# DischargeModule.net
KiCad netlist of a schematic drawn in Altium Designer
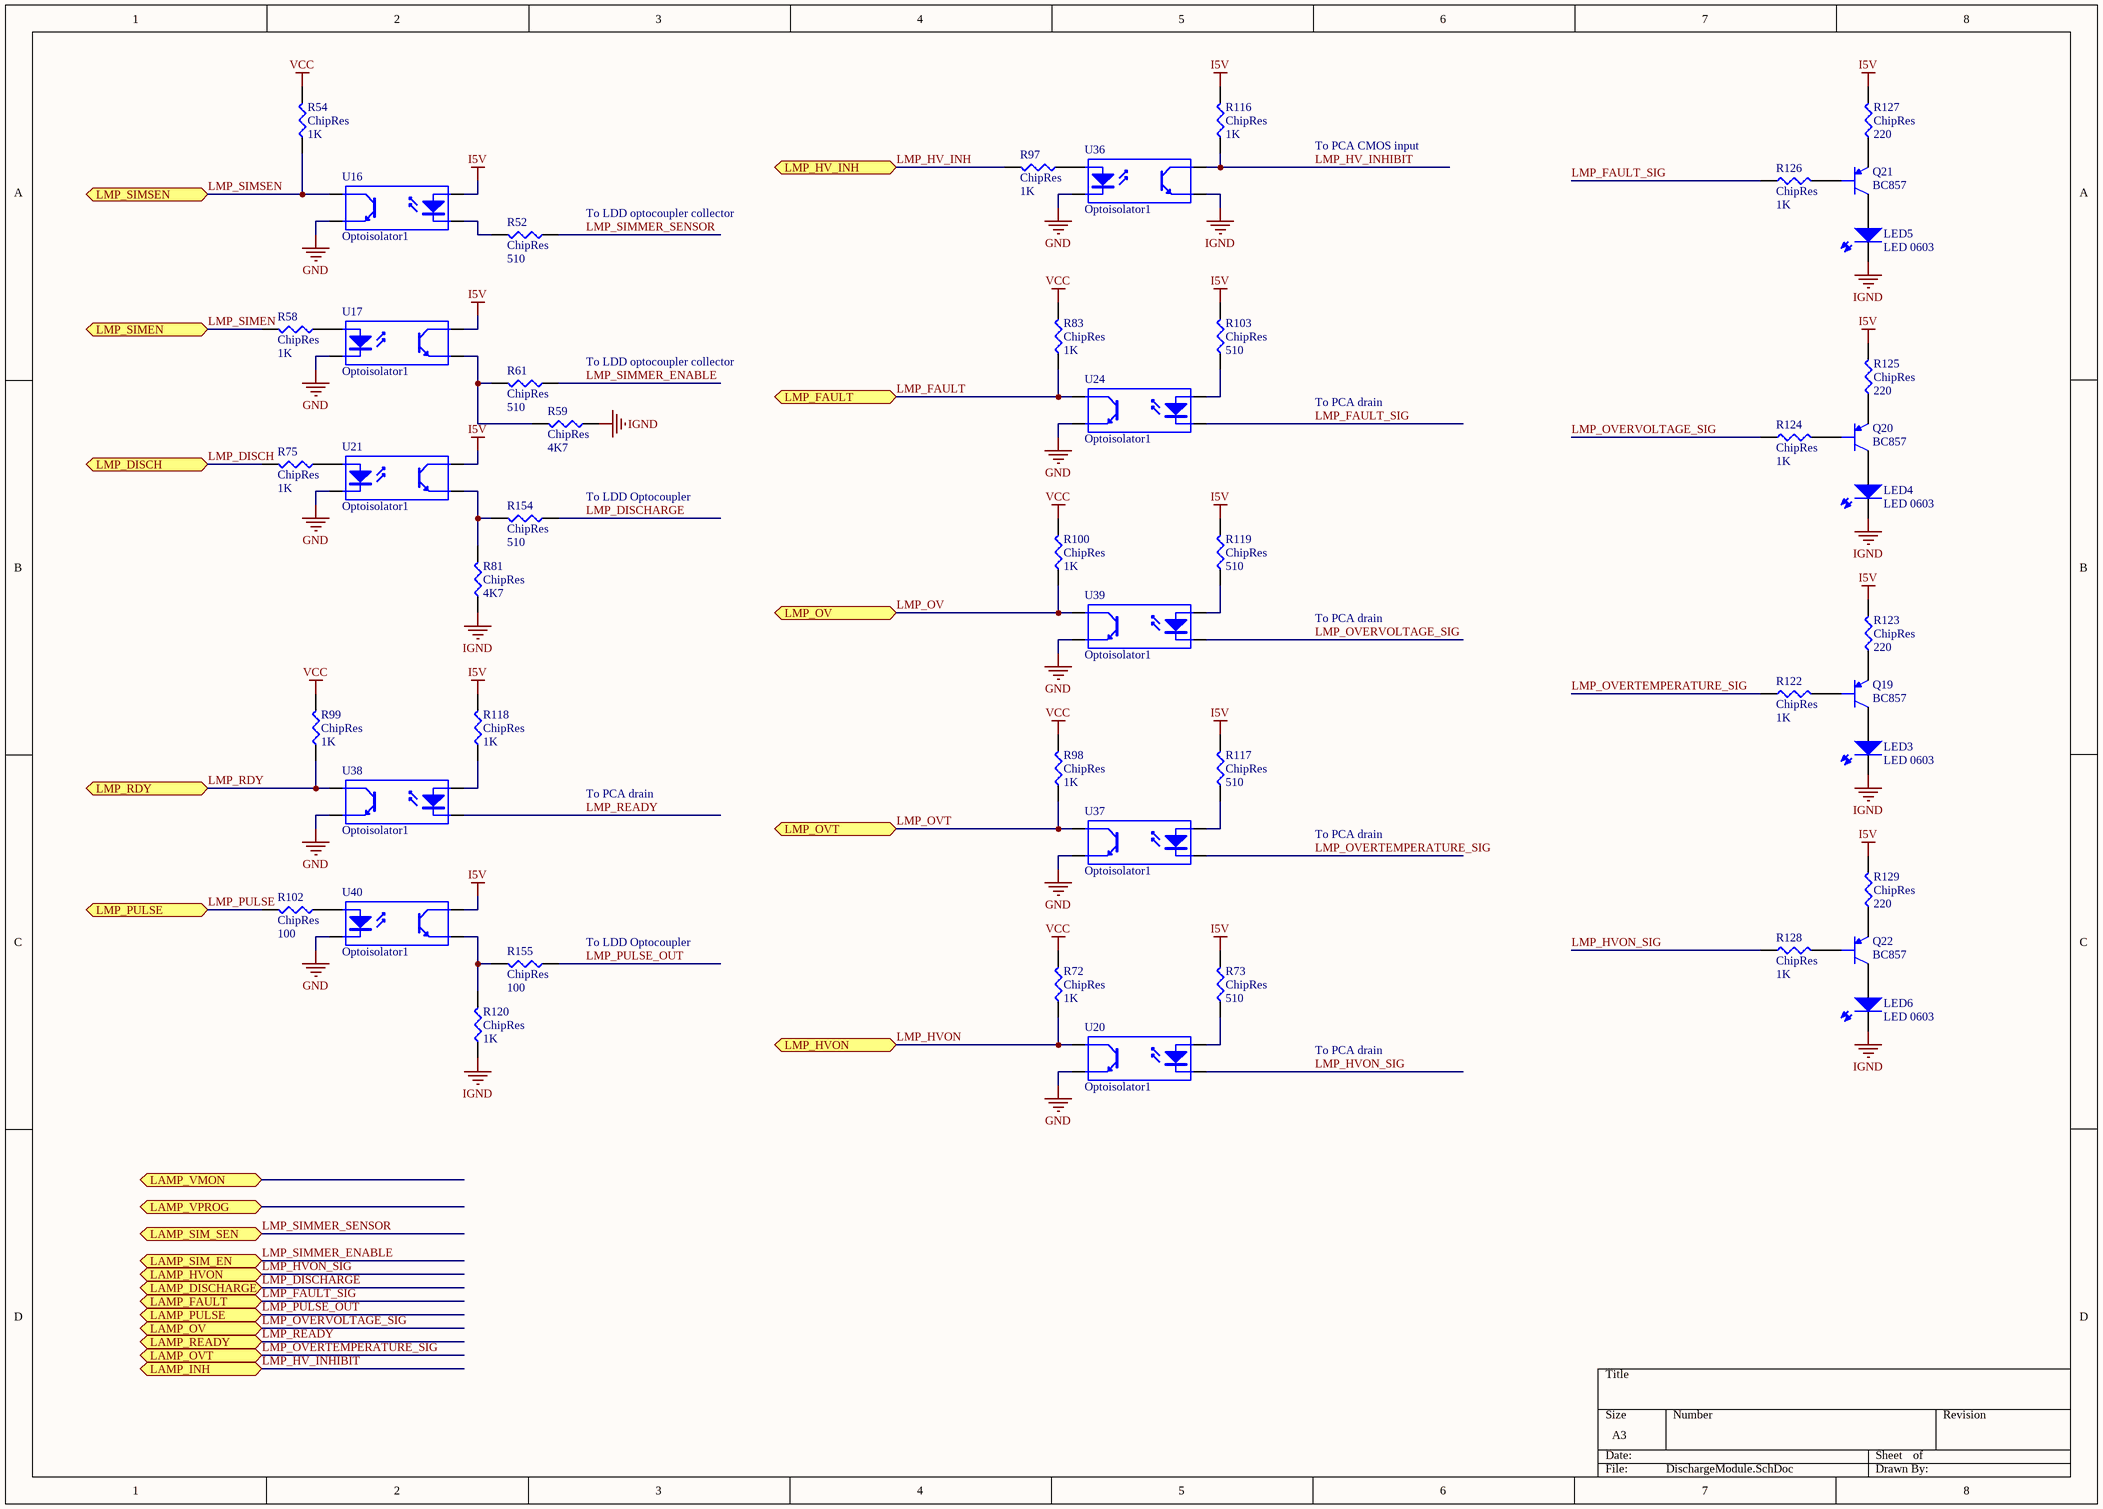
[diagram p0: DischargeModule.SchDoc]

(export (version "E")
  (design (tool "Eeschema 10.0.6"))
  (components
    (comp (ref "LED3") (value "LED 0603") (footprint "PLCC-2") (libsource (lib "LEDs") (part "LED0603")))
    (comp (ref "LED4") (value "LED 0603") (footprint "PLCC-2") (libsource (lib "LEDs") (part "LED0603")))
    (comp (ref "LED5") (value "LED 0603") (footprint "PLCC-2") (libsource (lib "LEDs") (part "LED0603")))
    (comp (ref "LED6") (value "LED 0603") (footprint "PLCC-2") (libsource (lib "LEDs") (part "LED0603")))
    (comp (ref "Q19")
      (value "BC857")
      (footprint "BJT:SOT23")
      (description "PNP Transistor")
      (libsource (lib "BJT") (part "BC857"))
    )
    (comp (ref "Q20")
      (value "BC857")
      (footprint "BJT:SOT23")
      (description "PNP Transistor")
      (libsource (lib "BJT") (part "BC857"))
    )
    (comp (ref "Q21")
      (value "BC857")
      (footprint "BJT:SOT23")
      (description "PNP Transistor")
      (libsource (lib "BJT") (part "BC857"))
    )
    (comp (ref "Q22")
      (value "BC857")
      (footprint "BJT:SOT23")
      (description "PNP Transistor")
      (libsource (lib "BJT") (part "BC857"))
    )
    (comp (ref "R52")
      (value "ChipRes")
      (footprint "RES0805")
      (description "Chip resistor")
      (fields (field (name "ALTIUM_VALUE") "510"))
      (libsource (lib "Common Devices") (part "ChipRes"))
    )
    (comp (ref "R54")
      (value "ChipRes")
      (footprint "RES0805")
      (description "Chip resistor")
      (fields (field (name "ALTIUM_VALUE") "1K"))
      (libsource (lib "Common Devices") (part "ChipRes"))
    )
    (comp (ref "R58")
      (value "ChipRes")
      (footprint "RES0805")
      (description "Chip resistor")
      (fields (field (name "ALTIUM_VALUE") "1K"))
      (libsource (lib "Common Devices") (part "ChipRes"))
    )
    (comp (ref "R59")
      (value "ChipRes")
      (footprint "RES0805")
      (description "Chip resistor")
      (fields (field (name "ALTIUM_VALUE") "4K7"))
      (libsource (lib "Common Devices") (part "ChipRes"))
    )
    (comp (ref "R61")
      (value "ChipRes")
      (footprint "RES0805")
      (description "Chip resistor")
      (fields (field (name "ALTIUM_VALUE") "510"))
      (libsource (lib "Common Devices") (part "ChipRes"))
    )
    (comp (ref "R72")
      (value "ChipRes")
      (footprint "RES0805")
      (description "Chip resistor")
      (fields (field (name "ALTIUM_VALUE") "1K"))
      (libsource (lib "Common Devices") (part "ChipRes"))
    )
    (comp (ref "R73")
      (value "ChipRes")
      (footprint "RES0805")
      (description "Chip resistor")
      (fields (field (name "ALTIUM_VALUE") "510"))
      (libsource (lib "Common Devices") (part "ChipRes"))
    )
    (comp (ref "R75")
      (value "ChipRes")
      (footprint "RES0805")
      (description "Chip resistor")
      (fields (field (name "ALTIUM_VALUE") "1K"))
      (libsource (lib "Common Devices") (part "ChipRes"))
    )
    (comp (ref "R81")
      (value "ChipRes")
      (footprint "RES0805")
      (description "Chip resistor")
      (fields (field (name "ALTIUM_VALUE") "4K7"))
      (libsource (lib "Common Devices") (part "ChipRes"))
    )
    (comp (ref "R83")
      (value "ChipRes")
      (footprint "RES0805")
      (description "Chip resistor")
      (fields (field (name "ALTIUM_VALUE") "1K"))
      (libsource (lib "Common Devices") (part "ChipRes"))
    )
    (comp (ref "R97")
      (value "ChipRes")
      (footprint "RES0805")
      (description "Chip resistor")
      (fields (field (name "ALTIUM_VALUE") "1K"))
      (libsource (lib "Common Devices") (part "ChipRes"))
    )
    (comp (ref "R98")
      (value "ChipRes")
      (footprint "RES0805")
      (description "Chip resistor")
      (fields (field (name "ALTIUM_VALUE") "1K"))
      (libsource (lib "Common Devices") (part "ChipRes"))
    )
    (comp (ref "R99")
      (value "ChipRes")
      (footprint "RES0805")
      (description "Chip resistor")
      (fields (field (name "ALTIUM_VALUE") "1K"))
      (libsource (lib "Common Devices") (part "ChipRes"))
    )
    (comp (ref "R100")
      (value "ChipRes")
      (footprint "RES0805")
      (description "Chip resistor")
      (fields (field (name "ALTIUM_VALUE") "1K"))
      (libsource (lib "Common Devices") (part "ChipRes"))
    )
    (comp (ref "R102")
      (value "ChipRes")
      (footprint "RES0805")
      (description "Chip resistor")
      (fields (field (name "ALTIUM_VALUE") "100"))
      (libsource (lib "Common Devices") (part "ChipRes"))
    )
    (comp (ref "R103")
      (value "ChipRes")
      (footprint "RES0805")
      (description "Chip resistor")
      (fields (field (name "ALTIUM_VALUE") "510"))
      (libsource (lib "Common Devices") (part "ChipRes"))
    )
    (comp (ref "R116")
      (value "ChipRes")
      (footprint "RES0805")
      (description "Chip resistor")
      (fields (field (name "ALTIUM_VALUE") "1K"))
      (libsource (lib "Common Devices") (part "ChipRes"))
    )
    (comp (ref "R117")
      (value "ChipRes")
      (footprint "RES0805")
      (description "Chip resistor")
      (fields (field (name "ALTIUM_VALUE") "510"))
      (libsource (lib "Common Devices") (part "ChipRes"))
    )
    (comp (ref "R118")
      (value "ChipRes")
      (footprint "RES0805")
      (description "Chip resistor")
      (fields (field (name "ALTIUM_VALUE") "1K"))
      (libsource (lib "Common Devices") (part "ChipRes"))
    )
    (comp (ref "R119")
      (value "ChipRes")
      (footprint "RES0805")
      (description "Chip resistor")
      (fields (field (name "ALTIUM_VALUE") "510"))
      (libsource (lib "Common Devices") (part "ChipRes"))
    )
    (comp (ref "R120")
      (value "ChipRes")
      (footprint "RES0805")
      (description "Chip resistor")
      (fields (field (name "ALTIUM_VALUE") "1K"))
      (libsource (lib "Common Devices") (part "ChipRes"))
    )
    (comp (ref "R122")
      (value "ChipRes")
      (footprint "RES0805")
      (description "Chip resistor")
      (fields (field (name "ALTIUM_VALUE") "1K"))
      (libsource (lib "Common Devices") (part "ChipRes"))
    )
    (comp (ref "R123")
      (value "ChipRes")
      (footprint "RES0805")
      (description "Chip resistor")
      (fields (field (name "ALTIUM_VALUE") "220"))
      (libsource (lib "Common Devices") (part "ChipRes"))
    )
    (comp (ref "R124")
      (value "ChipRes")
      (footprint "RES0805")
      (description "Chip resistor")
      (fields (field (name "ALTIUM_VALUE") "1K"))
      (libsource (lib "Common Devices") (part "ChipRes"))
    )
    (comp (ref "R125")
      (value "ChipRes")
      (footprint "RES0805")
      (description "Chip resistor")
      (fields (field (name "ALTIUM_VALUE") "220"))
      (libsource (lib "Common Devices") (part "ChipRes"))
    )
    (comp (ref "R126")
      (value "ChipRes")
      (footprint "RES0805")
      (description "Chip resistor")
      (fields (field (name "ALTIUM_VALUE") "1K"))
      (libsource (lib "Common Devices") (part "ChipRes"))
    )
    (comp (ref "R127")
      (value "ChipRes")
      (footprint "RES0805")
      (description "Chip resistor")
      (fields (field (name "ALTIUM_VALUE") "220"))
      (libsource (lib "Common Devices") (part "ChipRes"))
    )
    (comp (ref "R128")
      (value "ChipRes")
      (footprint "RES0805")
      (description "Chip resistor")
      (fields (field (name "ALTIUM_VALUE") "1K"))
      (libsource (lib "Common Devices") (part "ChipRes"))
    )
    (comp (ref "R129")
      (value "ChipRes")
      (footprint "RES0805")
      (description "Chip resistor")
      (fields (field (name "ALTIUM_VALUE") "220"))
      (libsource (lib "Common Devices") (part "ChipRes"))
    )
    (comp (ref "R154")
      (value "ChipRes")
      (footprint "RES0805")
      (description "Chip resistor")
      (fields (field (name "ALTIUM_VALUE") "510"))
      (libsource (lib "Common Devices") (part "ChipRes"))
    )
    (comp (ref "R155")
      (value "ChipRes")
      (footprint "RES0805")
      (description "Chip resistor")
      (fields (field (name "ALTIUM_VALUE") "100"))
      (libsource (lib "Common Devices") (part "ChipRes"))
    )
    (comp (ref "U16")
      (value "Optoisolator1")
      (footprint "DIP-4")
      (description "4-Pin Phototransistor Optocoupler")
      (fields (field (name "PUBLISHER") "Altium Limited"))
      (libsource (lib "Miscellaneous Devices") (part "Optoisolator1"))
    )
    (comp (ref "U17")
      (value "Optoisolator1")
      (footprint "DIP-4")
      (description "4-Pin Phototransistor Optocoupler")
      (fields (field (name "PUBLISHER") "Altium Limited"))
      (libsource (lib "Miscellaneous Devices") (part "Optoisolator1"))
    )
    (comp (ref "U20")
      (value "Optoisolator1")
      (footprint "DIP-4")
      (description "4-Pin Phototransistor Optocoupler")
      (fields (field (name "PUBLISHER") "Altium Limited"))
      (libsource (lib "Miscellaneous Devices") (part "Optoisolator1"))
    )
    (comp (ref "U21")
      (value "Optoisolator1")
      (footprint "DIP-4")
      (description "4-Pin Phototransistor Optocoupler")
      (fields (field (name "PUBLISHER") "Altium Limited"))
      (libsource (lib "Miscellaneous Devices") (part "Optoisolator1"))
    )
    (comp (ref "U24")
      (value "Optoisolator1")
      (footprint "DIP-4")
      (description "4-Pin Phototransistor Optocoupler")
      (fields (field (name "PUBLISHER") "Altium Limited"))
      (libsource (lib "Miscellaneous Devices") (part "Optoisolator1"))
    )
    (comp (ref "U36")
      (value "Optoisolator1")
      (footprint "DIP-4")
      (description "4-Pin Phototransistor Optocoupler")
      (fields (field (name "PUBLISHER") "Altium Limited"))
      (libsource (lib "Miscellaneous Devices") (part "Optoisolator1"))
    )
    (comp (ref "U37")
      (value "Optoisolator1")
      (footprint "DIP-4")
      (description "4-Pin Phototransistor Optocoupler")
      (fields (field (name "PUBLISHER") "Altium Limited"))
      (libsource (lib "Miscellaneous Devices") (part "Optoisolator1"))
    )
    (comp (ref "U38")
      (value "Optoisolator1")
      (footprint "DIP-4")
      (description "4-Pin Phototransistor Optocoupler")
      (fields (field (name "PUBLISHER") "Altium Limited"))
      (libsource (lib "Miscellaneous Devices") (part "Optoisolator1"))
    )
    (comp (ref "U39")
      (value "Optoisolator1")
      (footprint "DIP-4")
      (description "4-Pin Phototransistor Optocoupler")
      (fields (field (name "PUBLISHER") "Altium Limited"))
      (libsource (lib "Miscellaneous Devices") (part "Optoisolator1"))
    )
    (comp (ref "U40")
      (value "Optoisolator1")
      (footprint "DIP-4")
      (description "4-Pin Phototransistor Optocoupler")
      (fields (field (name "PUBLISHER") "Altium Limited"))
      (libsource (lib "Miscellaneous Devices") (part "Optoisolator1"))
    )
  )
  (nets
    (net (code "3") (name "/LMP_DISCH") (class "Default") (node (ref "R75") (pin "2") (pintype "passive")))
    (net (code "4") (name "/LMP_DISCHARGE") (class "Default")
      (node (ref "R154") (pin "1") (pintype "passive"))
    )
    (net (code "5") (name "/LMP_FAULT") (class "Default")
      (node (ref "R83") (pin "1") (pintype "passive"))
      (node (ref "U24") (pin "4") (pinfunction "C_4") (pintype "passive"))
    )
    (net (code "6") (name "/LMP_FAULT_SIG") (class "Default")
      (node (ref "R126") (pin "1") (pintype "passive"))
      (node (ref "U24") (pin "2") (pinfunction "K_2") (pintype "passive"))
    )
    (net (code "7") (name "/LMP_HVON") (class "Default")
      (node (ref "R72") (pin "1") (pintype "passive"))
      (node (ref "U20") (pin "4") (pinfunction "C_4") (pintype "passive"))
    )
    (net (code "8") (name "/LMP_HVON_SIG") (class "Default")
      (node (ref "R128") (pin "1") (pintype "passive"))
      (node (ref "U20") (pin "2") (pinfunction "K_2") (pintype "passive"))
    )
    (net (code "9") (name "/LMP_HV_INH") (class "Default") (node (ref "R97") (pin "2") (pintype "passive")))
    (net (code "10") (name "/LMP_HV_INHIBIT") (class "Default")
      (node (ref "R116") (pin "1") (pintype "passive"))
      (node (ref "U36") (pin "4") (pinfunction "C_4") (pintype "passive"))
    )
    (net (code "11") (name "/LMP_OV") (class "Default")
      (node (ref "R100") (pin "1") (pintype "passive"))
      (node (ref "U39") (pin "4") (pinfunction "C_4") (pintype "passive"))
    )
    (net (code "12") (name "/LMP_OVERTEMPERATURE_SIG") (class "Default")
      (node (ref "R122") (pin "1") (pintype "passive"))
      (node (ref "U37") (pin "2") (pinfunction "K_2") (pintype "passive"))
    )
    (net (code "13") (name "/LMP_OVERVOLTAGE_SIG") (class "Default")
      (node (ref "R124") (pin "1") (pintype "passive"))
      (node (ref "U39") (pin "2") (pinfunction "K_2") (pintype "passive"))
    )
    (net (code "14") (name "/LMP_OVT") (class "Default")
      (node (ref "R98") (pin "1") (pintype "passive"))
      (node (ref "U37") (pin "4") (pinfunction "C_4") (pintype "passive"))
    )
    (net (code "15") (name "/LMP_PULSE") (class "Default") (node (ref "R102") (pin "2") (pintype "passive")))
    (net (code "16") (name "/LMP_PULSE_OUT") (class "Default")
      (node (ref "R155") (pin "1") (pintype "passive"))
    )
    (net (code "17") (name "/LMP_RDY") (class "Default")
      (node (ref "R99") (pin "1") (pintype "passive"))
      (node (ref "U38") (pin "4") (pinfunction "C_4") (pintype "passive"))
    )
    (net (code "18") (name "/LMP_READY") (class "Default")
      (node (ref "U38") (pin "2") (pinfunction "K_2") (pintype "passive"))
    )
    (net (code "19") (name "/LMP_SIMEN") (class "Default") (node (ref "R58") (pin "2") (pintype "passive")))
    (net (code "20") (name "/LMP_SIMMER_ENABLE") (class "Default")
      (node (ref "R61") (pin "1") (pintype "passive"))
    )
    (net (code "21") (name "/LMP_SIMMER_SENSOR") (class "Default")
      (node (ref "R52") (pin "1") (pintype "passive"))
    )
    (net (code "22") (name "/LMP_SIMSEN") (class "Default")
      (node (ref "R54") (pin "1") (pintype "passive"))
      (node (ref "U16") (pin "4") (pinfunction "C_4") (pintype "passive"))
    )
    (net (code "23") (name "GND") (class "Default")
      (node (ref "U16") (pin "3") (pinfunction "E_3") (pintype "passive"))
      (node (ref "U17") (pin "2") (pinfunction "K_2") (pintype "passive"))
      (node (ref "U20") (pin "3") (pinfunction "E_3") (pintype "passive"))
      (node (ref "U21") (pin "2") (pinfunction "K_2") (pintype "passive"))
      (node (ref "U24") (pin "3") (pinfunction "E_3") (pintype "passive"))
      (node (ref "U36") (pin "2") (pinfunction "K_2") (pintype "passive"))
      (node (ref "U37") (pin "3") (pinfunction "E_3") (pintype "passive"))
      (node (ref "U38") (pin "3") (pinfunction "E_3") (pintype "passive"))
      (node (ref "U39") (pin "3") (pinfunction "E_3") (pintype "passive"))
      (node (ref "U40") (pin "2") (pinfunction "K_2") (pintype "passive"))
    )
    (net (code "24") (name "I5V") (class "Default")
      (node (ref "R103") (pin "2") (pintype "passive"))
      (node (ref "R116") (pin "2") (pintype "passive"))
      (node (ref "R117") (pin "2") (pintype "passive"))
      (node (ref "R118") (pin "2") (pintype "passive"))
      (node (ref "R119") (pin "2") (pintype "passive"))
      (node (ref "R123") (pin "2") (pintype "passive"))
      (node (ref "R125") (pin "2") (pintype "passive"))
      (node (ref "R127") (pin "2") (pintype "passive"))
      (node (ref "R129") (pin "2") (pintype "passive"))
      (node (ref "R73") (pin "2") (pintype "passive"))
      (node (ref "U16") (pin "1") (pinfunction "A_1") (pintype "passive"))
      (node (ref "U17") (pin "4") (pinfunction "C_4") (pintype "passive"))
      (node (ref "U21") (pin "4") (pinfunction "C_4") (pintype "passive"))
      (node (ref "U40") (pin "4") (pinfunction "C_4") (pintype "passive"))
    )
    (net (code "25") (name "IGND") (class "Default")
      (node (ref "LED3") (pin "1") (pinfunction "1_1") (pintype "passive"))
      (node (ref "LED4") (pin "1") (pinfunction "1_1") (pintype "passive"))
      (node (ref "LED5") (pin "1") (pinfunction "1_1") (pintype "passive"))
      (node (ref "LED6") (pin "1") (pinfunction "1_1") (pintype "passive"))
      (node (ref "R120") (pin "1") (pintype "passive"))
      (node (ref "R59") (pin "1") (pintype "passive"))
      (node (ref "R81") (pin "1") (pintype "passive"))
      (node (ref "U36") (pin "3") (pinfunction "E_3") (pintype "passive"))
    )
    (net (code "26") (name "Net-(LED3-Pad2)") (class "Default")
      (node (ref "LED3") (pin "2") (pinfunction "2_2") (pintype "passive"))
      (node (ref "Q19") (pin "3") (pinfunction "3_3") (pintype "passive"))
    )
    (net (code "27") (name "Net-(LED4-Pad2)") (class "Default")
      (node (ref "LED4") (pin "2") (pinfunction "2_2") (pintype "passive"))
      (node (ref "Q20") (pin "3") (pinfunction "3_3") (pintype "passive"))
    )
    (net (code "28") (name "Net-(LED5-Pad2)") (class "Default")
      (node (ref "LED5") (pin "2") (pinfunction "2_2") (pintype "passive"))
      (node (ref "Q21") (pin "3") (pinfunction "3_3") (pintype "passive"))
    )
    (net (code "29") (name "Net-(LED6-Pad2)") (class "Default")
      (node (ref "LED6") (pin "2") (pinfunction "2_2") (pintype "passive"))
      (node (ref "Q22") (pin "3") (pinfunction "3_3") (pintype "passive"))
    )
    (net (code "30") (name "Net-(Q19-Pad1)") (class "Default")
      (node (ref "Q19") (pin "1") (pinfunction "1_1") (pintype "passive"))
      (node (ref "R122") (pin "2") (pintype "passive"))
    )
    (net (code "31") (name "Net-(Q19-Pad2)") (class "Default")
      (node (ref "Q19") (pin "2") (pinfunction "2_2") (pintype "passive"))
      (node (ref "R123") (pin "1") (pintype "passive"))
    )
    (net (code "32") (name "Net-(Q20-Pad1)") (class "Default")
      (node (ref "Q20") (pin "1") (pinfunction "1_1") (pintype "passive"))
      (node (ref "R124") (pin "2") (pintype "passive"))
    )
    (net (code "33") (name "Net-(Q20-Pad2)") (class "Default")
      (node (ref "Q20") (pin "2") (pinfunction "2_2") (pintype "passive"))
      (node (ref "R125") (pin "1") (pintype "passive"))
    )
    (net (code "34") (name "Net-(Q21-Pad1)") (class "Default")
      (node (ref "Q21") (pin "1") (pinfunction "1_1") (pintype "passive"))
      (node (ref "R126") (pin "2") (pintype "passive"))
    )
    (net (code "35") (name "Net-(Q21-Pad2)") (class "Default")
      (node (ref "Q21") (pin "2") (pinfunction "2_2") (pintype "passive"))
      (node (ref "R127") (pin "1") (pintype "passive"))
    )
    (net (code "36") (name "Net-(Q22-Pad1)") (class "Default")
      (node (ref "Q22") (pin "1") (pinfunction "1_1") (pintype "passive"))
      (node (ref "R128") (pin "2") (pintype "passive"))
    )
    (net (code "37") (name "Net-(Q22-Pad2)") (class "Default")
      (node (ref "Q22") (pin "2") (pinfunction "2_2") (pintype "passive"))
      (node (ref "R129") (pin "1") (pintype "passive"))
    )
    (net (code "38") (name "Net-(U16-K)") (class "Default")
      (node (ref "R52") (pin "2") (pintype "passive"))
      (node (ref "U16") (pin "2") (pinfunction "K_2") (pintype "passive"))
    )
    (net (code "39") (name "Net-(U17-A)") (class "Default")
      (node (ref "R58") (pin "1") (pintype "passive"))
      (node (ref "U17") (pin "1") (pinfunction "A_1") (pintype "passive"))
    )
    (net (code "40") (name "Net-(U17-E)") (class "Default")
      (node (ref "R59") (pin "2") (pintype "passive"))
      (node (ref "R61") (pin "2") (pintype "passive"))
      (node (ref "U17") (pin "3") (pinfunction "E_3") (pintype "passive"))
    )
    (net (code "41") (name "Net-(U20-A)") (class "Default")
      (node (ref "R73") (pin "1") (pintype "passive"))
      (node (ref "U20") (pin "1") (pinfunction "A_1") (pintype "passive"))
    )
    (net (code "42") (name "Net-(U21-A)") (class "Default")
      (node (ref "R75") (pin "1") (pintype "passive"))
      (node (ref "U21") (pin "1") (pinfunction "A_1") (pintype "passive"))
    )
    (net (code "43") (name "Net-(U21-E)") (class "Default")
      (node (ref "R154") (pin "2") (pintype "passive"))
      (node (ref "R81") (pin "2") (pintype "passive"))
      (node (ref "U21") (pin "3") (pinfunction "E_3") (pintype "passive"))
    )
    (net (code "44") (name "Net-(U24-A)") (class "Default")
      (node (ref "R103") (pin "1") (pintype "passive"))
      (node (ref "U24") (pin "1") (pinfunction "A_1") (pintype "passive"))
    )
    (net (code "45") (name "Net-(U36-A)") (class "Default")
      (node (ref "R97") (pin "1") (pintype "passive"))
      (node (ref "U36") (pin "1") (pinfunction "A_1") (pintype "passive"))
    )
    (net (code "46") (name "Net-(U37-A)") (class "Default")
      (node (ref "R117") (pin "1") (pintype "passive"))
      (node (ref "U37") (pin "1") (pinfunction "A_1") (pintype "passive"))
    )
    (net (code "47") (name "Net-(U38-A)") (class "Default")
      (node (ref "R118") (pin "1") (pintype "passive"))
      (node (ref "U38") (pin "1") (pinfunction "A_1") (pintype "passive"))
    )
    (net (code "48") (name "Net-(U39-A)") (class "Default")
      (node (ref "R119") (pin "1") (pintype "passive"))
      (node (ref "U39") (pin "1") (pinfunction "A_1") (pintype "passive"))
    )
    (net (code "49") (name "Net-(U40-A)") (class "Default")
      (node (ref "R102") (pin "1") (pintype "passive"))
      (node (ref "U40") (pin "1") (pinfunction "A_1") (pintype "passive"))
    )
    (net (code "50") (name "Net-(U40-E)") (class "Default")
      (node (ref "R120") (pin "2") (pintype "passive"))
      (node (ref "R155") (pin "2") (pintype "passive"))
      (node (ref "U40") (pin "3") (pinfunction "E_3") (pintype "passive"))
    )
    (net (code "51") (name "VCC") (class "Default")
      (node (ref "R100") (pin "2") (pintype "passive"))
      (node (ref "R54") (pin "2") (pintype "passive"))
      (node (ref "R72") (pin "2") (pintype "passive"))
      (node (ref "R83") (pin "2") (pintype "passive"))
      (node (ref "R98") (pin "2") (pintype "passive"))
      (node (ref "R99") (pin "2") (pintype "passive"))
    )
  )
)
